# 08-DPLL-2.net
KiCad netlist of a schematic drawn in Altium Designer
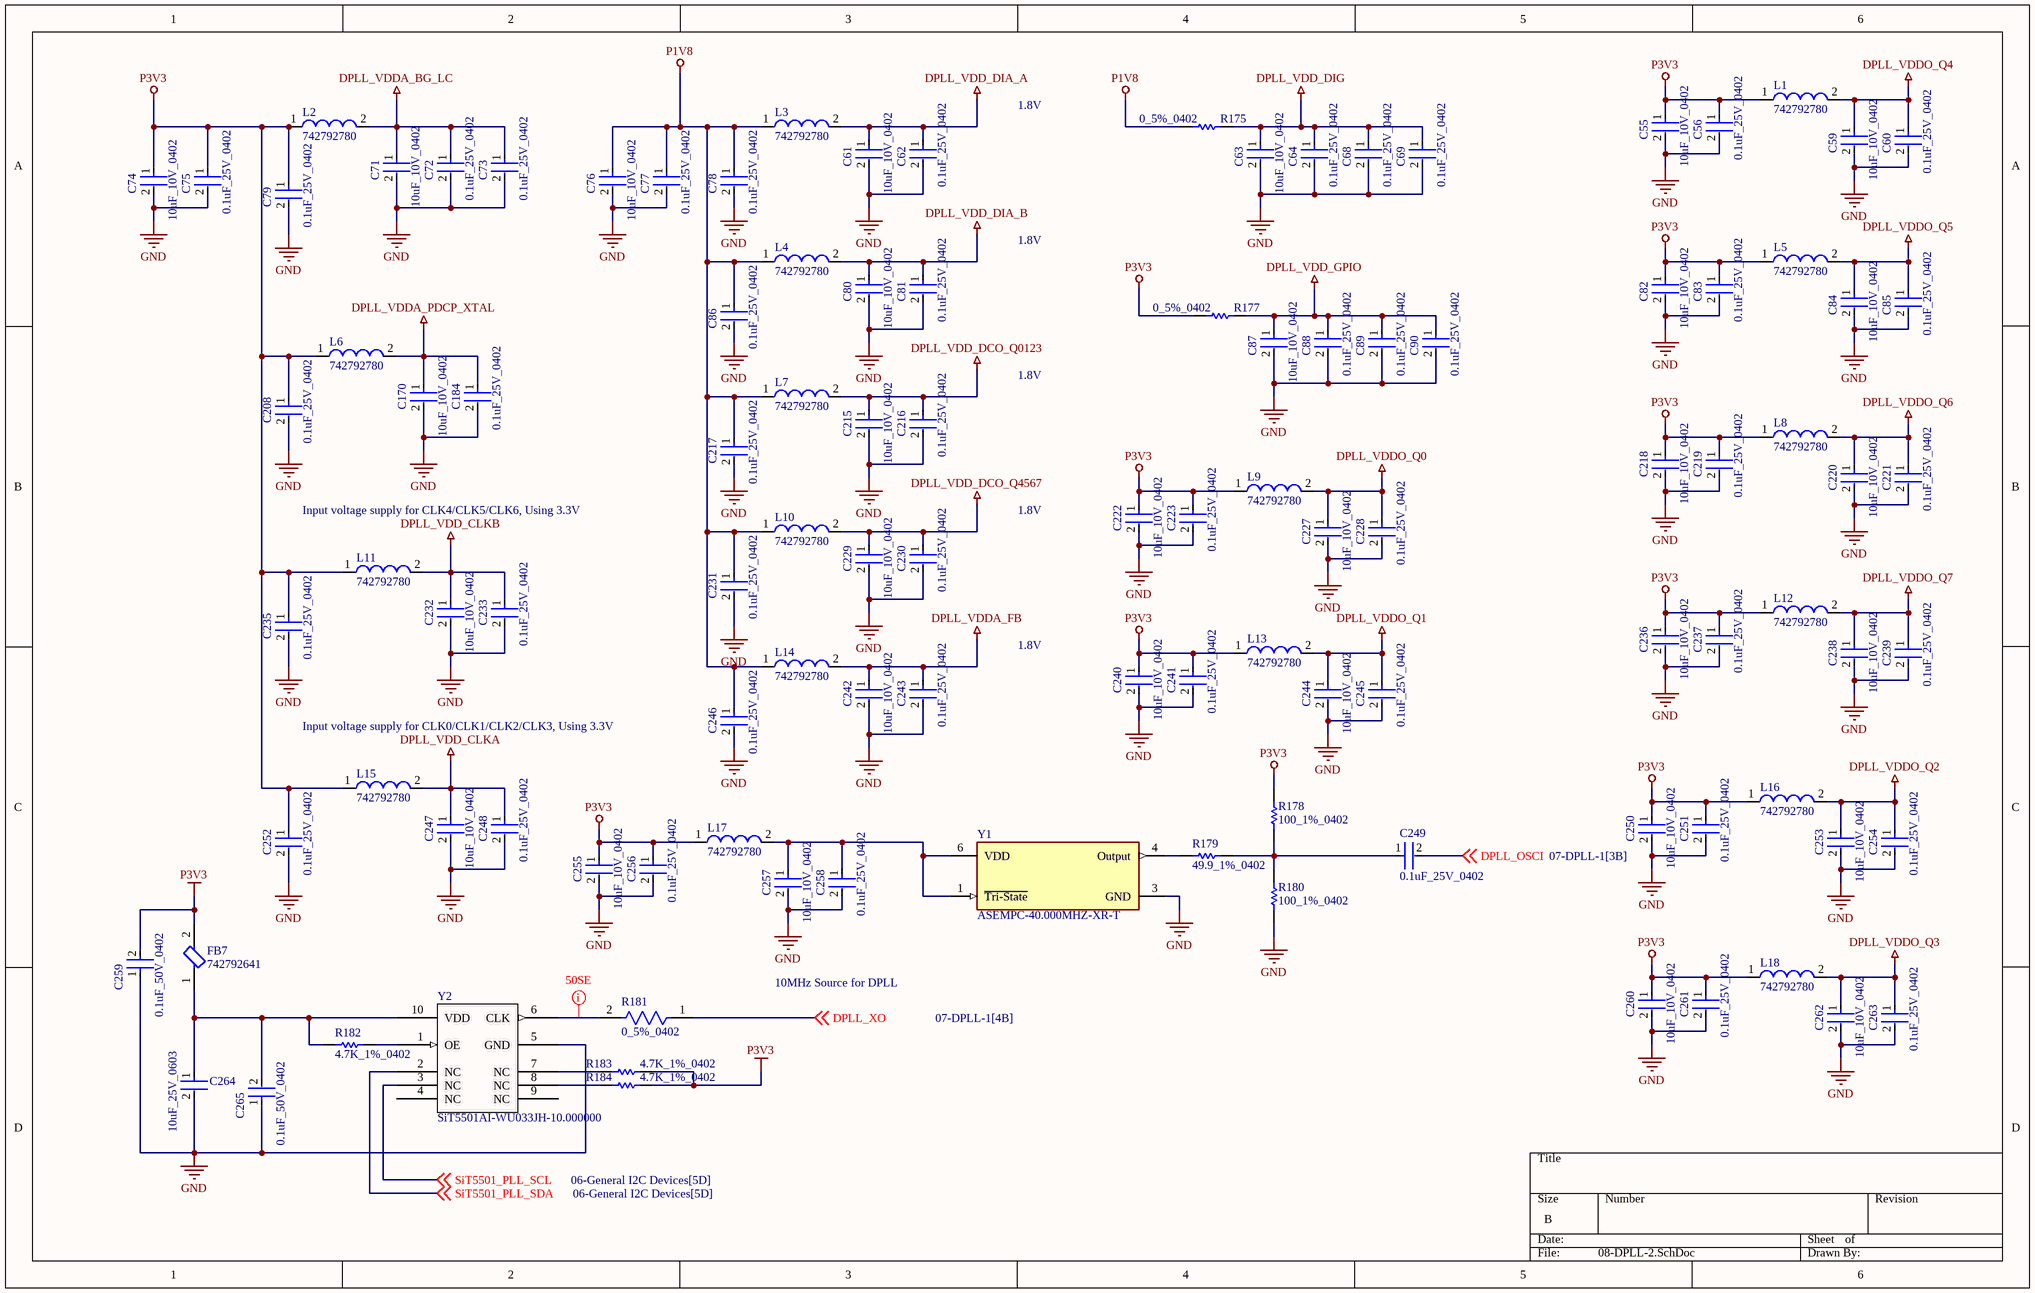
[diagram p0: 08-DPLL-2.SchDoc]

(export (version "E")
  (design (tool "Eeschema 10.0.6"))
  (components
    (comp (ref "C55")
      (value "10uF_10V_0402")
      (footprint "FP-CL05A106MP5NUNC-MFG")
      (description "CAP CER 10UF 10V X5R 0402")
      (fields
        (field (name "OCTOPART") "https://octopart.com/cl05a106mp5nunc-samsung-22457395")
        (field (name "TOLERANCE") "20%")
      )
      (libsource (lib "Altium Content Vault") (part "b4654b650e69147ec39a6b967a45e02"))
    )
    (comp (ref "C56")
      (value "0.1uF_25V_0402")
      (footprint "FP-0402-L_1_0_1-W_0_5_0_1-IPC_C")
      (description "General Purpose Ceramic Capacitor, 0402, 100nF, 10%, X7R, 15%, 25V")
      (fields (field (name "VOLTAGE") "25V") (field (name "TOLERANCE") "10%"))
      (libsource (lib "Altium Content Vault") (part "b4654b650e69147ec39a6b967a45e02"))
    )
    (comp (ref "C59")
      (value "10uF_10V_0402")
      (footprint "FP-CL05A106MP5NUNC-MFG")
      (description "CAP CER 10UF 10V X5R 0402")
      (fields
        (field (name "OCTOPART") "https://octopart.com/cl05a106mp5nunc-samsung-22457395")
        (field (name "TOLERANCE") "20%")
      )
      (libsource (lib "Altium Content Vault") (part "b4654b650e69147ec39a6b967a45e02"))
    )
    (comp (ref "C60")
      (value "0.1uF_25V_0402")
      (footprint "FP-0402-L_1_0_1-W_0_5_0_1-IPC_C")
      (description "General Purpose Ceramic Capacitor, 0402, 100nF, 10%, X7R, 15%, 25V")
      (fields (field (name "VOLTAGE") "25V") (field (name "TOLERANCE") "10%"))
      (libsource (lib "Altium Content Vault") (part "b4654b650e69147ec39a6b967a45e02"))
    )
    (comp (ref "C61")
      (value "10uF_10V_0402")
      (footprint "FP-CL05A106MP5NUNC-MFG")
      (description "CAP CER 10UF 10V X5R 0402")
      (fields
        (field (name "OCTOPART") "https://octopart.com/cl05a106mp5nunc-samsung-22457395")
        (field (name "TOLERANCE") "20%")
      )
      (libsource (lib "Altium Content Vault") (part "b4654b650e69147ec39a6b967a45e02"))
    )
    (comp (ref "C62")
      (value "0.1uF_25V_0402")
      (footprint "FP-0402-L_1_0_1-W_0_5_0_1-IPC_C")
      (description "General Purpose Ceramic Capacitor, 0402, 100nF, 10%, X7R, 15%, 25V")
      (fields (field (name "VOLTAGE") "25V") (field (name "TOLERANCE") "10%"))
      (libsource (lib "Altium Content Vault") (part "b4654b650e69147ec39a6b967a45e02"))
    )
    (comp (ref "C63")
      (value "10uF_10V_0402")
      (footprint "FP-CL05A106MP5NUNC-MFG")
      (description "CAP CER 10UF 10V X5R 0402")
      (fields
        (field (name "OCTOPART") "https://octopart.com/cl05a106mp5nunc-samsung-22457395")
        (field (name "TOLERANCE") "20%")
      )
      (libsource (lib "Altium Content Vault") (part "b4654b650e69147ec39a6b967a45e02"))
    )
    (comp (ref "C64")
      (value "0.1uF_25V_0402")
      (footprint "FP-0402-L_1_0_1-W_0_5_0_1-IPC_C")
      (description "General Purpose Ceramic Capacitor, 0402, 100nF, 10%, X7R, 15%, 25V")
      (fields (field (name "VOLTAGE") "25V") (field (name "TOLERANCE") "10%"))
      (libsource (lib "Altium Content Vault") (part "b4654b650e69147ec39a6b967a45e02"))
    )
    (comp (ref "C68")
      (value "0.1uF_25V_0402")
      (footprint "FP-0402-L_1_0_1-W_0_5_0_1-IPC_C")
      (description "General Purpose Ceramic Capacitor, 0402, 100nF, 10%, X7R, 15%, 25V")
      (fields (field (name "VOLTAGE") "25V") (field (name "TOLERANCE") "10%"))
      (libsource (lib "Altium Content Vault") (part "b4654b650e69147ec39a6b967a45e02"))
    )
    (comp (ref "C69")
      (value "0.1uF_25V_0402")
      (footprint "FP-0402-L_1_0_1-W_0_5_0_1-IPC_C")
      (description "General Purpose Ceramic Capacitor, 0402, 100nF, 10%, X7R, 15%, 25V")
      (fields (field (name "VOLTAGE") "25V") (field (name "TOLERANCE") "10%"))
      (libsource (lib "Altium Content Vault") (part "b4654b650e69147ec39a6b967a45e02"))
    )
    (comp (ref "C71")
      (value "10uF_10V_0402")
      (footprint "FP-CL05A106MP5NUNC-MFG")
      (description "CAP CER 10UF 10V X5R 0402")
      (fields
        (field (name "OCTOPART") "https://octopart.com/cl05a106mp5nunc-samsung-22457395")
        (field (name "TOLERANCE") "20%")
      )
      (libsource (lib "Altium Content Vault") (part "b4654b650e69147ec39a6b967a45e02"))
    )
    (comp (ref "C72")
      (value "0.1uF_25V_0402")
      (footprint "FP-0402-L_1_0_1-W_0_5_0_1-IPC_C")
      (description "General Purpose Ceramic Capacitor, 0402, 100nF, 10%, X7R, 15%, 25V")
      (fields (field (name "VOLTAGE") "25V") (field (name "TOLERANCE") "10%"))
      (libsource (lib "Altium Content Vault") (part "b4654b650e69147ec39a6b967a45e02"))
    )
    (comp (ref "C73")
      (value "0.1uF_25V_0402")
      (footprint "FP-0402-L_1_0_1-W_0_5_0_1-IPC_C")
      (description "General Purpose Ceramic Capacitor, 0402, 100nF, 10%, X7R, 15%, 25V")
      (fields (field (name "VOLTAGE") "25V") (field (name "TOLERANCE") "10%"))
      (libsource (lib "Altium Content Vault") (part "b4654b650e69147ec39a6b967a45e02"))
    )
    (comp (ref "C74")
      (value "10uF_10V_0402")
      (footprint "FP-CL05A106MP5NUNC-MFG")
      (description "CAP CER 10UF 10V X5R 0402")
      (fields
        (field (name "OCTOPART") "https://octopart.com/cl05a106mp5nunc-samsung-22457395")
        (field (name "TOLERANCE") "20%")
      )
      (libsource (lib "Altium Content Vault") (part "b4654b650e69147ec39a6b967a45e02"))
    )
    (comp (ref "C75")
      (value "0.1uF_25V_0402")
      (footprint "FP-0402-L_1_0_1-W_0_5_0_1-IPC_C")
      (description "General Purpose Ceramic Capacitor, 0402, 100nF, 10%, X7R, 15%, 25V")
      (fields (field (name "VOLTAGE") "25V") (field (name "TOLERANCE") "10%"))
      (libsource (lib "Altium Content Vault") (part "b4654b650e69147ec39a6b967a45e02"))
    )
    (comp (ref "C76")
      (value "10uF_10V_0402")
      (footprint "FP-CL05A106MP5NUNC-MFG")
      (description "CAP CER 10UF 10V X5R 0402")
      (fields
        (field (name "OCTOPART") "https://octopart.com/cl05a106mp5nunc-samsung-22457395")
        (field (name "TOLERANCE") "20%")
      )
      (libsource (lib "Altium Content Vault") (part "b4654b650e69147ec39a6b967a45e02"))
    )
    (comp (ref "C77")
      (value "0.1uF_25V_0402")
      (footprint "FP-0402-L_1_0_1-W_0_5_0_1-IPC_C")
      (description "General Purpose Ceramic Capacitor, 0402, 100nF, 10%, X7R, 15%, 25V")
      (fields (field (name "VOLTAGE") "25V") (field (name "TOLERANCE") "10%"))
      (libsource (lib "Altium Content Vault") (part "b4654b650e69147ec39a6b967a45e02"))
    )
    (comp (ref "C78")
      (value "0.1uF_25V_0402")
      (footprint "FP-0402-L_1_0_1-W_0_5_0_1-IPC_C")
      (description "General Purpose Ceramic Capacitor, 0402, 100nF, 10%, X7R, 15%, 25V")
      (fields (field (name "VOLTAGE") "25V") (field (name "TOLERANCE") "10%"))
      (libsource (lib "Altium Content Vault") (part "b4654b650e69147ec39a6b967a45e02"))
    )
    (comp (ref "C79")
      (value "0.1uF_25V_0402")
      (footprint "FP-0402-L_1_0_1-W_0_5_0_1-IPC_C")
      (description "General Purpose Ceramic Capacitor, 0402, 100nF, 10%, X7R, 15%, 25V")
      (fields (field (name "VOLTAGE") "25V") (field (name "TOLERANCE") "10%"))
      (libsource (lib "Altium Content Vault") (part "b4654b650e69147ec39a6b967a45e02"))
    )
    (comp (ref "C80")
      (value "10uF_10V_0402")
      (footprint "FP-CL05A106MP5NUNC-MFG")
      (description "CAP CER 10UF 10V X5R 0402")
      (fields
        (field (name "OCTOPART") "https://octopart.com/cl05a106mp5nunc-samsung-22457395")
        (field (name "TOLERANCE") "20%")
      )
      (libsource (lib "Altium Content Vault") (part "b4654b650e69147ec39a6b967a45e02"))
    )
    (comp (ref "C81")
      (value "0.1uF_25V_0402")
      (footprint "FP-0402-L_1_0_1-W_0_5_0_1-IPC_C")
      (description "General Purpose Ceramic Capacitor, 0402, 100nF, 10%, X7R, 15%, 25V")
      (fields (field (name "VOLTAGE") "25V") (field (name "TOLERANCE") "10%"))
      (libsource (lib "Altium Content Vault") (part "b4654b650e69147ec39a6b967a45e02"))
    )
    (comp (ref "C82")
      (value "10uF_10V_0402")
      (footprint "FP-CL05A106MP5NUNC-MFG")
      (description "CAP CER 10UF 10V X5R 0402")
      (fields
        (field (name "OCTOPART") "https://octopart.com/cl05a106mp5nunc-samsung-22457395")
        (field (name "TOLERANCE") "20%")
      )
      (libsource (lib "Altium Content Vault") (part "b4654b650e69147ec39a6b967a45e02"))
    )
    (comp (ref "C83")
      (value "0.1uF_25V_0402")
      (footprint "FP-0402-L_1_0_1-W_0_5_0_1-IPC_C")
      (description "General Purpose Ceramic Capacitor, 0402, 100nF, 10%, X7R, 15%, 25V")
      (fields (field (name "VOLTAGE") "25V") (field (name "TOLERANCE") "10%"))
      (libsource (lib "Altium Content Vault") (part "b4654b650e69147ec39a6b967a45e02"))
    )
    (comp (ref "C84")
      (value "10uF_10V_0402")
      (footprint "FP-CL05A106MP5NUNC-MFG")
      (description "CAP CER 10UF 10V X5R 0402")
      (fields
        (field (name "OCTOPART") "https://octopart.com/cl05a106mp5nunc-samsung-22457395")
        (field (name "TOLERANCE") "20%")
      )
      (libsource (lib "Altium Content Vault") (part "b4654b650e69147ec39a6b967a45e02"))
    )
    (comp (ref "C85")
      (value "0.1uF_25V_0402")
      (footprint "FP-0402-L_1_0_1-W_0_5_0_1-IPC_C")
      (description "General Purpose Ceramic Capacitor, 0402, 100nF, 10%, X7R, 15%, 25V")
      (fields (field (name "VOLTAGE") "25V") (field (name "TOLERANCE") "10%"))
      (libsource (lib "Altium Content Vault") (part "b4654b650e69147ec39a6b967a45e02"))
    )
    (comp (ref "C86")
      (value "0.1uF_25V_0402")
      (footprint "FP-0402-L_1_0_1-W_0_5_0_1-IPC_C")
      (description "General Purpose Ceramic Capacitor, 0402, 100nF, 10%, X7R, 15%, 25V")
      (fields (field (name "VOLTAGE") "25V") (field (name "TOLERANCE") "10%"))
      (libsource (lib "Altium Content Vault") (part "b4654b650e69147ec39a6b967a45e02"))
    )
    (comp (ref "C87")
      (value "10uF_10V_0402")
      (footprint "FP-CL05A106MP5NUNC-MFG")
      (description "CAP CER 10UF 10V X5R 0402")
      (fields
        (field (name "OCTOPART") "https://octopart.com/cl05a106mp5nunc-samsung-22457395")
        (field (name "TOLERANCE") "20%")
      )
      (libsource (lib "Altium Content Vault") (part "b4654b650e69147ec39a6b967a45e02"))
    )
    (comp (ref "C88")
      (value "0.1uF_25V_0402")
      (footprint "FP-0402-L_1_0_1-W_0_5_0_1-IPC_C")
      (description "General Purpose Ceramic Capacitor, 0402, 100nF, 10%, X7R, 15%, 25V")
      (fields (field (name "VOLTAGE") "25V") (field (name "TOLERANCE") "10%"))
      (libsource (lib "Altium Content Vault") (part "b4654b650e69147ec39a6b967a45e02"))
    )
    (comp (ref "C89")
      (value "0.1uF_25V_0402")
      (footprint "FP-0402-L_1_0_1-W_0_5_0_1-IPC_C")
      (description "General Purpose Ceramic Capacitor, 0402, 100nF, 10%, X7R, 15%, 25V")
      (fields (field (name "VOLTAGE") "25V") (field (name "TOLERANCE") "10%"))
      (libsource (lib "Altium Content Vault") (part "b4654b650e69147ec39a6b967a45e02"))
    )
    (comp (ref "C90")
      (value "0.1uF_25V_0402")
      (footprint "FP-0402-L_1_0_1-W_0_5_0_1-IPC_C")
      (description "General Purpose Ceramic Capacitor, 0402, 100nF, 10%, X7R, 15%, 25V")
      (fields (field (name "VOLTAGE") "25V") (field (name "TOLERANCE") "10%"))
      (libsource (lib "Altium Content Vault") (part "b4654b650e69147ec39a6b967a45e02"))
    )
    (comp (ref "C170")
      (value "10uF_10V_0402")
      (footprint "FP-CL05A106MP5NUNC-MFG")
      (description "CAP CER 10UF 10V X5R 0402")
      (fields
        (field (name "OCTOPART") "https://octopart.com/cl05a106mp5nunc-samsung-22457395")
        (field (name "TOLERANCE") "20%")
      )
      (libsource (lib "Altium Content Vault") (part "b4654b650e69147ec39a6b967a45e02"))
    )
    (comp (ref "C184")
      (value "0.1uF_25V_0402")
      (footprint "FP-0402-L_1_0_1-W_0_5_0_1-IPC_C")
      (description "General Purpose Ceramic Capacitor, 0402, 100nF, 10%, X7R, 15%, 25V")
      (fields (field (name "VOLTAGE") "25V") (field (name "TOLERANCE") "10%"))
      (libsource (lib "Altium Content Vault") (part "b4654b650e69147ec39a6b967a45e02"))
    )
    (comp (ref "C208")
      (value "0.1uF_25V_0402")
      (footprint "FP-0402-L_1_0_1-W_0_5_0_1-IPC_C")
      (description "General Purpose Ceramic Capacitor, 0402, 100nF, 10%, X7R, 15%, 25V")
      (fields (field (name "VOLTAGE") "25V") (field (name "TOLERANCE") "10%"))
      (libsource (lib "Altium Content Vault") (part "b4654b650e69147ec39a6b967a45e02"))
    )
    (comp (ref "C215")
      (value "10uF_10V_0402")
      (footprint "FP-CL05A106MP5NUNC-MFG")
      (description "CAP CER 10UF 10V X5R 0402")
      (fields
        (field (name "OCTOPART") "https://octopart.com/cl05a106mp5nunc-samsung-22457395")
        (field (name "TOLERANCE") "20%")
      )
      (libsource (lib "Altium Content Vault") (part "b4654b650e69147ec39a6b967a45e02"))
    )
    (comp (ref "C216")
      (value "0.1uF_25V_0402")
      (footprint "FP-0402-L_1_0_1-W_0_5_0_1-IPC_C")
      (description "General Purpose Ceramic Capacitor, 0402, 100nF, 10%, X7R, 15%, 25V")
      (fields (field (name "VOLTAGE") "25V") (field (name "TOLERANCE") "10%"))
      (libsource (lib "Altium Content Vault") (part "b4654b650e69147ec39a6b967a45e02"))
    )
    (comp (ref "C217")
      (value "0.1uF_25V_0402")
      (footprint "FP-0402-L_1_0_1-W_0_5_0_1-IPC_C")
      (description "General Purpose Ceramic Capacitor, 0402, 100nF, 10%, X7R, 15%, 25V")
      (fields (field (name "VOLTAGE") "25V") (field (name "TOLERANCE") "10%"))
      (libsource (lib "Altium Content Vault") (part "b4654b650e69147ec39a6b967a45e02"))
    )
    (comp (ref "C218")
      (value "10uF_10V_0402")
      (footprint "FP-CL05A106MP5NUNC-MFG")
      (description "CAP CER 10UF 10V X5R 0402")
      (fields
        (field (name "OCTOPART") "https://octopart.com/cl05a106mp5nunc-samsung-22457395")
        (field (name "TOLERANCE") "20%")
      )
      (libsource (lib "Altium Content Vault") (part "b4654b650e69147ec39a6b967a45e02"))
    )
    (comp (ref "C219")
      (value "0.1uF_25V_0402")
      (footprint "FP-0402-L_1_0_1-W_0_5_0_1-IPC_C")
      (description "General Purpose Ceramic Capacitor, 0402, 100nF, 10%, X7R, 15%, 25V")
      (fields (field (name "VOLTAGE") "25V") (field (name "TOLERANCE") "10%"))
      (libsource (lib "Altium Content Vault") (part "b4654b650e69147ec39a6b967a45e02"))
    )
    (comp (ref "C220")
      (value "10uF_10V_0402")
      (footprint "FP-CL05A106MP5NUNC-MFG")
      (description "CAP CER 10UF 10V X5R 0402")
      (fields
        (field (name "OCTOPART") "https://octopart.com/cl05a106mp5nunc-samsung-22457395")
        (field (name "TOLERANCE") "20%")
      )
      (libsource (lib "Altium Content Vault") (part "b4654b650e69147ec39a6b967a45e02"))
    )
    (comp (ref "C221")
      (value "0.1uF_25V_0402")
      (footprint "FP-0402-L_1_0_1-W_0_5_0_1-IPC_C")
      (description "General Purpose Ceramic Capacitor, 0402, 100nF, 10%, X7R, 15%, 25V")
      (fields (field (name "VOLTAGE") "25V") (field (name "TOLERANCE") "10%"))
      (libsource (lib "Altium Content Vault") (part "b4654b650e69147ec39a6b967a45e02"))
    )
    (comp (ref "C222")
      (value "10uF_10V_0402")
      (footprint "FP-CL05A106MP5NUNC-MFG")
      (description "CAP CER 10UF 10V X5R 0402")
      (fields
        (field (name "OCTOPART") "https://octopart.com/cl05a106mp5nunc-samsung-22457395")
        (field (name "TOLERANCE") "20%")
      )
      (libsource (lib "Altium Content Vault") (part "b4654b650e69147ec39a6b967a45e02"))
    )
    (comp (ref "C223")
      (value "0.1uF_25V_0402")
      (footprint "FP-0402-L_1_0_1-W_0_5_0_1-IPC_C")
      (description "General Purpose Ceramic Capacitor, 0402, 100nF, 10%, X7R, 15%, 25V")
      (fields (field (name "VOLTAGE") "25V") (field (name "TOLERANCE") "10%"))
      (libsource (lib "Altium Content Vault") (part "b4654b650e69147ec39a6b967a45e02"))
    )
    (comp (ref "C227")
      (value "10uF_10V_0402")
      (footprint "FP-CL05A106MP5NUNC-MFG")
      (description "CAP CER 10UF 10V X5R 0402")
      (fields
        (field (name "OCTOPART") "https://octopart.com/cl05a106mp5nunc-samsung-22457395")
        (field (name "TOLERANCE") "20%")
      )
      (libsource (lib "Altium Content Vault") (part "b4654b650e69147ec39a6b967a45e02"))
    )
    (comp (ref "C228")
      (value "0.1uF_25V_0402")
      (footprint "FP-0402-L_1_0_1-W_0_5_0_1-IPC_C")
      (description "General Purpose Ceramic Capacitor, 0402, 100nF, 10%, X7R, 15%, 25V")
      (fields (field (name "VOLTAGE") "25V") (field (name "TOLERANCE") "10%"))
      (libsource (lib "Altium Content Vault") (part "b4654b650e69147ec39a6b967a45e02"))
    )
    (comp (ref "C229")
      (value "10uF_10V_0402")
      (footprint "FP-CL05A106MP5NUNC-MFG")
      (description "CAP CER 10UF 10V X5R 0402")
      (fields
        (field (name "OCTOPART") "https://octopart.com/cl05a106mp5nunc-samsung-22457395")
        (field (name "TOLERANCE") "20%")
      )
      (libsource (lib "Altium Content Vault") (part "b4654b650e69147ec39a6b967a45e02"))
    )
    (comp (ref "C230")
      (value "0.1uF_25V_0402")
      (footprint "FP-0402-L_1_0_1-W_0_5_0_1-IPC_C")
      (description "General Purpose Ceramic Capacitor, 0402, 100nF, 10%, X7R, 15%, 25V")
      (fields (field (name "VOLTAGE") "25V") (field (name "TOLERANCE") "10%"))
      (libsource (lib "Altium Content Vault") (part "b4654b650e69147ec39a6b967a45e02"))
    )
    (comp (ref "C231")
      (value "0.1uF_25V_0402")
      (footprint "FP-0402-L_1_0_1-W_0_5_0_1-IPC_C")
      (description "General Purpose Ceramic Capacitor, 0402, 100nF, 10%, X7R, 15%, 25V")
      (fields (field (name "VOLTAGE") "25V") (field (name "TOLERANCE") "10%"))
      (libsource (lib "Altium Content Vault") (part "b4654b650e69147ec39a6b967a45e02"))
    )
    (comp (ref "C232")
      (value "10uF_10V_0402")
      (footprint "FP-CL05A106MP5NUNC-MFG")
      (description "CAP CER 10UF 10V X5R 0402")
      (fields
        (field (name "OCTOPART") "https://octopart.com/cl05a106mp5nunc-samsung-22457395")
        (field (name "TOLERANCE") "20%")
      )
      (libsource (lib "Altium Content Vault") (part "b4654b650e69147ec39a6b967a45e02"))
    )
    (comp (ref "C233")
      (value "0.1uF_25V_0402")
      (footprint "FP-0402-L_1_0_1-W_0_5_0_1-IPC_C")
      (description "General Purpose Ceramic Capacitor, 0402, 100nF, 10%, X7R, 15%, 25V")
      (fields (field (name "VOLTAGE") "25V") (field (name "TOLERANCE") "10%"))
      (libsource (lib "Altium Content Vault") (part "b4654b650e69147ec39a6b967a45e02"))
    )
    (comp (ref "C235")
      (value "0.1uF_25V_0402")
      (footprint "FP-0402-L_1_0_1-W_0_5_0_1-IPC_C")
      (description "General Purpose Ceramic Capacitor, 0402, 100nF, 10%, X7R, 15%, 25V")
      (fields (field (name "VOLTAGE") "25V") (field (name "TOLERANCE") "10%"))
      (libsource (lib "Altium Content Vault") (part "b4654b650e69147ec39a6b967a45e02"))
    )
    (comp (ref "C236")
      (value "10uF_10V_0402")
      (footprint "FP-CL05A106MP5NUNC-MFG")
      (description "CAP CER 10UF 10V X5R 0402")
      (fields
        (field (name "OCTOPART") "https://octopart.com/cl05a106mp5nunc-samsung-22457395")
        (field (name "TOLERANCE") "20%")
      )
      (libsource (lib "Altium Content Vault") (part "b4654b650e69147ec39a6b967a45e02"))
    )
    (comp (ref "C237")
      (value "0.1uF_25V_0402")
      (footprint "FP-0402-L_1_0_1-W_0_5_0_1-IPC_C")
      (description "General Purpose Ceramic Capacitor, 0402, 100nF, 10%, X7R, 15%, 25V")
      (fields (field (name "VOLTAGE") "25V") (field (name "TOLERANCE") "10%"))
      (libsource (lib "Altium Content Vault") (part "b4654b650e69147ec39a6b967a45e02"))
    )
    (comp (ref "C238")
      (value "10uF_10V_0402")
      (footprint "FP-CL05A106MP5NUNC-MFG")
      (description "CAP CER 10UF 10V X5R 0402")
      (fields
        (field (name "OCTOPART") "https://octopart.com/cl05a106mp5nunc-samsung-22457395")
        (field (name "TOLERANCE") "20%")
      )
      (libsource (lib "Altium Content Vault") (part "b4654b650e69147ec39a6b967a45e02"))
    )
    (comp (ref "C239")
      (value "0.1uF_25V_0402")
      (footprint "FP-0402-L_1_0_1-W_0_5_0_1-IPC_C")
      (description "General Purpose Ceramic Capacitor, 0402, 100nF, 10%, X7R, 15%, 25V")
      (fields (field (name "VOLTAGE") "25V") (field (name "TOLERANCE") "10%"))
      (libsource (lib "Altium Content Vault") (part "b4654b650e69147ec39a6b967a45e02"))
    )
    (comp (ref "C240")
      (value "10uF_10V_0402")
      (footprint "FP-CL05A106MP5NUNC-MFG")
      (description "CAP CER 10UF 10V X5R 0402")
      (fields
        (field (name "OCTOPART") "https://octopart.com/cl05a106mp5nunc-samsung-22457395")
        (field (name "TOLERANCE") "20%")
      )
      (libsource (lib "Altium Content Vault") (part "b4654b650e69147ec39a6b967a45e02"))
    )
    (comp (ref "C241")
      (value "0.1uF_25V_0402")
      (footprint "FP-0402-L_1_0_1-W_0_5_0_1-IPC_C")
      (description "General Purpose Ceramic Capacitor, 0402, 100nF, 10%, X7R, 15%, 25V")
      (fields (field (name "VOLTAGE") "25V") (field (name "TOLERANCE") "10%"))
      (libsource (lib "Altium Content Vault") (part "b4654b650e69147ec39a6b967a45e02"))
    )
    (comp (ref "C242")
      (value "10uF_10V_0402")
      (footprint "FP-CL05A106MP5NUNC-MFG")
      (description "CAP CER 10UF 10V X5R 0402")
      (fields
        (field (name "OCTOPART") "https://octopart.com/cl05a106mp5nunc-samsung-22457395")
        (field (name "TOLERANCE") "20%")
      )
      (libsource (lib "Altium Content Vault") (part "b4654b650e69147ec39a6b967a45e02"))
    )
    (comp (ref "C243")
      (value "0.1uF_25V_0402")
      (footprint "FP-0402-L_1_0_1-W_0_5_0_1-IPC_C")
      (description "General Purpose Ceramic Capacitor, 0402, 100nF, 10%, X7R, 15%, 25V")
      (fields (field (name "VOLTAGE") "25V") (field (name "TOLERANCE") "10%"))
      (libsource (lib "Altium Content Vault") (part "b4654b650e69147ec39a6b967a45e02"))
    )
    (comp (ref "C244")
      (value "10uF_10V_0402")
      (footprint "FP-CL05A106MP5NUNC-MFG")
      (description "CAP CER 10UF 10V X5R 0402")
      (fields
        (field (name "OCTOPART") "https://octopart.com/cl05a106mp5nunc-samsung-22457395")
        (field (name "TOLERANCE") "20%")
      )
      (libsource (lib "Altium Content Vault") (part "b4654b650e69147ec39a6b967a45e02"))
    )
    (comp (ref "C245")
      (value "0.1uF_25V_0402")
      (footprint "FP-0402-L_1_0_1-W_0_5_0_1-IPC_C")
      (description "General Purpose Ceramic Capacitor, 0402, 100nF, 10%, X7R, 15%, 25V")
      (fields (field (name "VOLTAGE") "25V") (field (name "TOLERANCE") "10%"))
      (libsource (lib "Altium Content Vault") (part "b4654b650e69147ec39a6b967a45e02"))
    )
    (comp (ref "C246")
      (value "0.1uF_25V_0402")
      (footprint "FP-0402-L_1_0_1-W_0_5_0_1-IPC_C")
      (description "General Purpose Ceramic Capacitor, 0402, 100nF, 10%, X7R, 15%, 25V")
      (fields (field (name "VOLTAGE") "25V") (field (name "TOLERANCE") "10%"))
      (libsource (lib "Altium Content Vault") (part "b4654b650e69147ec39a6b967a45e02"))
    )
    (comp (ref "C247")
      (value "10uF_10V_0402")
      (footprint "FP-CL05A106MP5NUNC-MFG")
      (description "CAP CER 10UF 10V X5R 0402")
      (fields
        (field (name "OCTOPART") "https://octopart.com/cl05a106mp5nunc-samsung-22457395")
        (field (name "TOLERANCE") "20%")
      )
      (libsource (lib "Altium Content Vault") (part "b4654b650e69147ec39a6b967a45e02"))
    )
    (comp (ref "C248")
      (value "0.1uF_25V_0402")
      (footprint "FP-0402-L_1_0_1-W_0_5_0_1-IPC_C")
      (description "General Purpose Ceramic Capacitor, 0402, 100nF, 10%, X7R, 15%, 25V")
      (fields (field (name "VOLTAGE") "25V") (field (name "TOLERANCE") "10%"))
      (libsource (lib "Altium Content Vault") (part "b4654b650e69147ec39a6b967a45e02"))
    )
    (comp (ref "C249")
      (value "0.1uF_25V_0402")
      (footprint "FP-0402-L_1_0_1-W_0_5_0_1-IPC_C")
      (description "General Purpose Ceramic Capacitor, 0402, 100nF, 10%, X7R, 15%, 25V")
      (fields (field (name "VOLTAGE") "25V") (field (name "TOLERANCE") "10%"))
      (libsource (lib "Altium Content Vault") (part "b4654b650e69147ec39a6b967a45e02"))
    )
    (comp (ref "C250")
      (value "10uF_10V_0402")
      (footprint "FP-CL05A106MP5NUNC-MFG")
      (description "CAP CER 10UF 10V X5R 0402")
      (fields
        (field (name "OCTOPART") "https://octopart.com/cl05a106mp5nunc-samsung-22457395")
        (field (name "TOLERANCE") "20%")
      )
      (libsource (lib "Altium Content Vault") (part "b4654b650e69147ec39a6b967a45e02"))
    )
    (comp (ref "C251")
      (value "0.1uF_25V_0402")
      (footprint "FP-0402-L_1_0_1-W_0_5_0_1-IPC_C")
      (description "General Purpose Ceramic Capacitor, 0402, 100nF, 10%, X7R, 15%, 25V")
      (fields (field (name "VOLTAGE") "25V") (field (name "TOLERANCE") "10%"))
      (libsource (lib "Altium Content Vault") (part "b4654b650e69147ec39a6b967a45e02"))
    )
    (comp (ref "C252")
      (value "0.1uF_25V_0402")
      (footprint "FP-0402-L_1_0_1-W_0_5_0_1-IPC_C")
      (description "General Purpose Ceramic Capacitor, 0402, 100nF, 10%, X7R, 15%, 25V")
      (fields (field (name "VOLTAGE") "25V") (field (name "TOLERANCE") "10%"))
      (libsource (lib "Altium Content Vault") (part "b4654b650e69147ec39a6b967a45e02"))
    )
    (comp (ref "C253")
      (value "10uF_10V_0402")
      (footprint "FP-CL05A106MP5NUNC-MFG")
      (description "CAP CER 10UF 10V X5R 0402")
      (fields
        (field (name "OCTOPART") "https://octopart.com/cl05a106mp5nunc-samsung-22457395")
        (field (name "TOLERANCE") "20%")
      )
      (libsource (lib "Altium Content Vault") (part "b4654b650e69147ec39a6b967a45e02"))
    )
    (comp (ref "C254")
      (value "0.1uF_25V_0402")
      (footprint "FP-0402-L_1_0_1-W_0_5_0_1-IPC_C")
      (description "General Purpose Ceramic Capacitor, 0402, 100nF, 10%, X7R, 15%, 25V")
      (fields (field (name "VOLTAGE") "25V") (field (name "TOLERANCE") "10%"))
      (libsource (lib "Altium Content Vault") (part "b4654b650e69147ec39a6b967a45e02"))
    )
    (comp (ref "C255")
      (value "10uF_10V_0402")
      (footprint "FP-CL05A106MP5NUNC-MFG")
      (description "CAP CER 10UF 10V X5R 0402")
      (fields
        (field (name "OCTOPART") "https://octopart.com/cl05a106mp5nunc-samsung-22457395")
        (field (name "TOLERANCE") "20%")
      )
      (libsource (lib "Altium Content Vault") (part "b4654b650e69147ec39a6b967a45e02"))
    )
    (comp (ref "C256")
      (value "0.1uF_25V_0402")
      (footprint "FP-0402-L_1_0_1-W_0_5_0_1-IPC_C")
      (description "General Purpose Ceramic Capacitor, 0402, 100nF, 10%, X7R, 15%, 25V")
      (fields (field (name "VOLTAGE") "25V") (field (name "TOLERANCE") "10%"))
      (libsource (lib "Altium Content Vault") (part "b4654b650e69147ec39a6b967a45e02"))
    )
    (comp (ref "C257")
      (value "10uF_10V_0402")
      (footprint "FP-CL05A106MP5NUNC-MFG")
      (description "CAP CER 10UF 10V X5R 0402")
      (fields
        (field (name "OCTOPART") "https://octopart.com/cl05a106mp5nunc-samsung-22457395")
        (field (name "TOLERANCE") "20%")
      )
      (libsource (lib "Altium Content Vault") (part "b4654b650e69147ec39a6b967a45e02"))
    )
    (comp (ref "C258")
      (value "0.1uF_25V_0402")
      (footprint "FP-0402-L_1_0_1-W_0_5_0_1-IPC_C")
      (description "General Purpose Ceramic Capacitor, 0402, 100nF, 10%, X7R, 15%, 25V")
      (fields (field (name "VOLTAGE") "25V") (field (name "TOLERANCE") "10%"))
      (libsource (lib "Altium Content Vault") (part "b4654b650e69147ec39a6b967a45e02"))
    )
    (comp (ref "C259")
      (value "0.1uF_50V_0402")
      (footprint "FP-C1005-050-0_05-IPC_C")
      (description "Multilayer Ceramic Capacitors 100nF ±10% 50V X7R SMD 0402")
      (fields (field (name "VOLTAGE") "50V") (field (name "TOLERANCE") "10%"))
      (libsource (lib "Altium Content Vault") (part "b4654b650e69147ec39a6b967a45e02"))
    )
    (comp (ref "C260")
      (value "10uF_10V_0402")
      (footprint "FP-CL05A106MP5NUNC-MFG")
      (description "CAP CER 10UF 10V X5R 0402")
      (fields
        (field (name "OCTOPART") "https://octopart.com/cl05a106mp5nunc-samsung-22457395")
        (field (name "TOLERANCE") "20%")
      )
      (libsource (lib "Altium Content Vault") (part "b4654b650e69147ec39a6b967a45e02"))
    )
    (comp (ref "C261")
      (value "0.1uF_25V_0402")
      (footprint "FP-0402-L_1_0_1-W_0_5_0_1-IPC_C")
      (description "General Purpose Ceramic Capacitor, 0402, 100nF, 10%, X7R, 15%, 25V")
      (fields (field (name "VOLTAGE") "25V") (field (name "TOLERANCE") "10%"))
      (libsource (lib "Altium Content Vault") (part "b4654b650e69147ec39a6b967a45e02"))
    )
    (comp (ref "C262")
      (value "10uF_10V_0402")
      (footprint "FP-CL05A106MP5NUNC-MFG")
      (description "CAP CER 10UF 10V X5R 0402")
      (fields
        (field (name "OCTOPART") "https://octopart.com/cl05a106mp5nunc-samsung-22457395")
        (field (name "TOLERANCE") "20%")
      )
      (libsource (lib "Altium Content Vault") (part "b4654b650e69147ec39a6b967a45e02"))
    )
    (comp (ref "C263")
      (value "0.1uF_25V_0402")
      (footprint "FP-0402-L_1_0_1-W_0_5_0_1-IPC_C")
      (description "General Purpose Ceramic Capacitor, 0402, 100nF, 10%, X7R, 15%, 25V")
      (fields (field (name "VOLTAGE") "25V") (field (name "TOLERANCE") "10%"))
      (libsource (lib "Altium Content Vault") (part "b4654b650e69147ec39a6b967a45e02"))
    )
    (comp (ref "C264")
      (value "10uF_25V_0603")
      (footprint "FP-CL10-IPC_C")
      (description "Cap Ceramic 10uF 25V X5R ±20% Pad SMD 0603 +85°C T/R")
      (fields (field (name "TOLERANCE") "20%"))
      (libsource (lib "Altium Content Vault") (part "b4654b650e69147ec39a6b967a45e02"))
    )
    (comp (ref "C265")
      (value "0.1uF_50V_0402")
      (footprint "FP-C1005-050-0_05-IPC_C")
      (description "Multilayer Ceramic Capacitors 100nF ±10% 50V X7R SMD 0402")
      (fields (field (name "VOLTAGE") "50V") (field (name "TOLERANCE") "10%"))
      (libsource (lib "Altium Content Vault") (part "b4654b650e69147ec39a6b967a45e02"))
    )
    (comp (ref "FB7")
      (value "742792641")
      (footprint "FP-742792641-MFG")
      (description "FERRITE BEAD 300 OHM 0603 1LN")
      (fields (field (name "TOLERANCE") "25%"))
      (libsource (lib "Altium Content Vault") (part "5f30dd21d616792df468990f7003faa"))
    )
    (comp (ref "L1")
      (value "742792780")
      (footprint "SMD-0402")
      (description "SMD EMI Suppression Ferrite Bead WE-CBF, Z = 220 Ohm")
      (libsource (lib "Altium Content Vault") (part "PAS-IND-INDUCTOR-2"))
    )
    (comp (ref "L2")
      (value "742792780")
      (footprint "SMD-0402")
      (description "SMD EMI Suppression Ferrite Bead WE-CBF, Z = 220 Ohm")
      (libsource (lib "Altium Content Vault") (part "PAS-IND-INDUCTOR-2"))
    )
    (comp (ref "L3")
      (value "742792780")
      (footprint "SMD-0402")
      (description "SMD EMI Suppression Ferrite Bead WE-CBF, Z = 220 Ohm")
      (libsource (lib "Altium Content Vault") (part "PAS-IND-INDUCTOR-2"))
    )
    (comp (ref "L4")
      (value "742792780")
      (footprint "SMD-0402")
      (description "SMD EMI Suppression Ferrite Bead WE-CBF, Z = 220 Ohm")
      (libsource (lib "Altium Content Vault") (part "PAS-IND-INDUCTOR-2"))
    )
    (comp (ref "L5")
      (value "742792780")
      (footprint "SMD-0402")
      (description "SMD EMI Suppression Ferrite Bead WE-CBF, Z = 220 Ohm")
      (libsource (lib "Altium Content Vault") (part "PAS-IND-INDUCTOR-2"))
    )
    (comp (ref "L6")
      (value "742792780")
      (footprint "SMD-0402")
      (description "SMD EMI Suppression Ferrite Bead WE-CBF, Z = 220 Ohm")
      (libsource (lib "Altium Content Vault") (part "PAS-IND-INDUCTOR-2"))
    )
    (comp (ref "L7")
      (value "742792780")
      (footprint "SMD-0402")
      (description "SMD EMI Suppression Ferrite Bead WE-CBF, Z = 220 Ohm")
      (libsource (lib "Altium Content Vault") (part "PAS-IND-INDUCTOR-2"))
    )
    (comp (ref "L8")
      (value "742792780")
      (footprint "SMD-0402")
      (description "SMD EMI Suppression Ferrite Bead WE-CBF, Z = 220 Ohm")
      (libsource (lib "Altium Content Vault") (part "PAS-IND-INDUCTOR-2"))
    )
    (comp (ref "L9")
      (value "742792780")
      (footprint "SMD-0402")
      (description "SMD EMI Suppression Ferrite Bead WE-CBF, Z = 220 Ohm")
      (libsource (lib "Altium Content Vault") (part "PAS-IND-INDUCTOR-2"))
    )
    (comp (ref "L10")
      (value "742792780")
      (footprint "SMD-0402")
      (description "SMD EMI Suppression Ferrite Bead WE-CBF, Z = 220 Ohm")
      (libsource (lib "Altium Content Vault") (part "PAS-IND-INDUCTOR-2"))
    )
    (comp (ref "L11")
      (value "742792780")
      (footprint "SMD-0402")
      (description "SMD EMI Suppression Ferrite Bead WE-CBF, Z = 220 Ohm")
      (libsource (lib "Altium Content Vault") (part "PAS-IND-INDUCTOR-2"))
    )
    (comp (ref "L12")
      (value "742792780")
      (footprint "SMD-0402")
      (description "SMD EMI Suppression Ferrite Bead WE-CBF, Z = 220 Ohm")
      (libsource (lib "Altium Content Vault") (part "PAS-IND-INDUCTOR-2"))
    )
    (comp (ref "L13")
      (value "742792780")
      (footprint "SMD-0402")
      (description "SMD EMI Suppression Ferrite Bead WE-CBF, Z = 220 Ohm")
      (libsource (lib "Altium Content Vault") (part "PAS-IND-INDUCTOR-2"))
    )
    (comp (ref "L14")
      (value "742792780")
      (footprint "SMD-0402")
      (description "SMD EMI Suppression Ferrite Bead WE-CBF, Z = 220 Ohm")
      (libsource (lib "Altium Content Vault") (part "PAS-IND-INDUCTOR-2"))
    )
    (comp (ref "L15")
      (value "742792780")
      (footprint "SMD-0402")
      (description "SMD EMI Suppression Ferrite Bead WE-CBF, Z = 220 Ohm")
      (libsource (lib "Altium Content Vault") (part "PAS-IND-INDUCTOR-2"))
    )
    (comp (ref "L16")
      (value "742792780")
      (footprint "SMD-0402")
      (description "SMD EMI Suppression Ferrite Bead WE-CBF, Z = 220 Ohm")
      (libsource (lib "Altium Content Vault") (part "PAS-IND-INDUCTOR-2"))
    )
    (comp (ref "L17")
      (value "742792780")
      (footprint "SMD-0402")
      (description "SMD EMI Suppression Ferrite Bead WE-CBF, Z = 220 Ohm")
      (libsource (lib "Altium Content Vault") (part "PAS-IND-INDUCTOR-2"))
    )
    (comp (ref "L18")
      (value "742792780")
      (footprint "SMD-0402")
      (description "SMD EMI Suppression Ferrite Bead WE-CBF, Z = 220 Ohm")
      (libsource (lib "Altium Content Vault") (part "PAS-IND-INDUCTOR-2"))
    )
    (comp (ref "R175")
      (value "0_5%_0402")
      (footprint "RESC1005X40X25LL10T10")
      (fields (field (name "MANUFACTURER") "KOA Speer") (field (name "PART NUMBER") "RK73Z1ETTP"))
      (libsource (lib "Altium Content Vault") (part "RES"))
    )
    (comp (ref "R177")
      (value "0_5%_0402")
      (footprint "RESC1005X40X25LL10T10")
      (fields (field (name "MANUFACTURER") "KOA Speer") (field (name "PART NUMBER") "RK73Z1ETTP"))
      (libsource (lib "Altium Content Vault") (part "RES"))
    )
    (comp (ref "R178")
      (value "100_1%_0402")
      (footprint "RESC1005X40X25ML05T10")
      (fields (field (name "PART NUMBER") "ERJ-U02F1000X") (field (name "MANUFACTURER") "Panasonic"))
      (libsource (lib "Altium Content Vault") (part "RES"))
    )
    (comp (ref "R179")
      (value "49.9_1%_0402")
      (footprint "RESC1005X40X25NL10T10")
      (fields (field (name "PART NUMBER") "RK73H1ETTP49R9F") (field (name "MANUFACTURER") "KOA Speer"))
      (libsource (lib "Altium Content Vault") (part "RES"))
    )
    (comp (ref "R180")
      (value "100_1%_0402")
      (footprint "RESC1005X40X25ML05T10")
      (fields (field (name "PART NUMBER") "ERJ-U02F1000X") (field (name "MANUFACTURER") "Panasonic"))
      (libsource (lib "Altium Content Vault") (part "RES"))
    )
    (comp (ref "R181")
      (value "0_5%_0402")
      (footprint "FP-AC0402-0_37-IPC_B")
      (description "RESISTOR 0402 JUMPER ZERO OHM")
      (fields (field (name "TOLERANCE") "1%"))
      (libsource (lib "Altium Content Vault") (part "1029c3af85768c4190bb7ad29bc67b5"))
    )
    (comp (ref "R182")
      (value "4.7K_1%_0402")
      (footprint "RESC1005X40X25NL10T10")
      (fields (field (name "MANUFACTURER") "Bourns") (field (name "PART NUMBER") "CR0402-FX-4701GLF"))
      (libsource (lib "Altium Content Vault") (part "RES"))
    )
    (comp (ref "R183")
      (value "4.7K_1%_0402")
      (footprint "RESC1005X40X25NL10T10")
      (fields (field (name "MANUFACTURER") "Bourns") (field (name "PART NUMBER") "CR0402-FX-4701GLF"))
      (libsource (lib "Altium Content Vault") (part "RES"))
    )
    (comp (ref "R184")
      (value "4.7K_1%_0402")
      (footprint "RESC1005X40X25NL10T10")
      (fields (field (name "MANUFACTURER") "Bourns") (field (name "PART NUMBER") "CR0402-FX-4701GLF"))
      (libsource (lib "Altium Content Vault") (part "RES"))
    )
    (comp (ref "Y1")
      (value "ASEMPC-40.000MHZ-XR-T")
      (footprint "FP-ASEMP-CMOS-MFG")
      (description "MEMS Oscillator 40MHz ±25ppm CMOS 2.25V~3.6V 6-SMD 3.2mm x 2.5mm")
      (libsource (lib "Altium Content Vault") (part "9526c112e3a98a1af86e8f4e974a861"))
    )
    (comp (ref "Y2")
      (value "SiTime_SiT5501AC-WU-33E0-10T")
      (footprint "SITIME_SPL-086-CQFN-010-C07050_REV_DRAFT")
      (description "OSC, MEMS, STRATUM 3E, 10.000MHZ, 10PPB STAB, LVCMOS, 3.3V, O/P EN, 7.0X5.0X2.2MM, CQFN-10")
      (fields
        (field (name "MANUFACTURER PART NUMBER") "SiT5501AI-WU033JH-10.000000")
        (field (name "MANUFACTURER") "SiTime")
      )
      (libsource (lib "OCXO_DaughterCard") (part "CMP-OSC-00029-2"))
    )
  )
  (nets
    (net (code "1") (name "DPLL_OSCI") (class "Default")
      (node (ref "C249") (pin "2") (pinfunction "2_2") (pintype "passive"))
    )
    (net (code "2") (name "DPLL_VDDA_BG_LC") (class "Default")
      (node (ref "C71") (pin "1") (pinfunction "1_1") (pintype "passive"))
      (node (ref "C72") (pin "1") (pinfunction "1_1") (pintype "passive"))
      (node (ref "C73") (pin "1") (pinfunction "1_1") (pintype "passive"))
      (node (ref "L2") (pin "2") (pinfunction "2_2") (pintype "passive"))
    )
    (net (code "3") (name "DPLL_VDDA_FB") (class "Default")
      (node (ref "C242") (pin "1") (pinfunction "1_1") (pintype "passive"))
      (node (ref "C243") (pin "1") (pinfunction "1_1") (pintype "passive"))
      (node (ref "L14") (pin "2") (pinfunction "2_2") (pintype "passive"))
    )
    (net (code "4") (name "DPLL_VDDA_PDCP_XTAL") (class "Default")
      (node (ref "C170") (pin "1") (pinfunction "1_1") (pintype "passive"))
      (node (ref "C184") (pin "1") (pinfunction "1_1") (pintype "passive"))
      (node (ref "L6") (pin "2") (pinfunction "2_2") (pintype "passive"))
    )
    (net (code "5") (name "DPLL_VDDO_Q0") (class "Default")
      (node (ref "C227") (pin "1") (pinfunction "1_1") (pintype "passive"))
      (node (ref "C228") (pin "1") (pinfunction "1_1") (pintype "passive"))
      (node (ref "L9") (pin "2") (pinfunction "2_2") (pintype "passive"))
    )
    (net (code "6") (name "DPLL_VDDO_Q1") (class "Default")
      (node (ref "C244") (pin "1") (pinfunction "1_1") (pintype "passive"))
      (node (ref "C245") (pin "1") (pinfunction "1_1") (pintype "passive"))
      (node (ref "L13") (pin "2") (pinfunction "2_2") (pintype "passive"))
    )
    (net (code "7") (name "DPLL_VDDO_Q2") (class "Default")
      (node (ref "C253") (pin "1") (pinfunction "1_1") (pintype "passive"))
      (node (ref "C254") (pin "1") (pinfunction "1_1") (pintype "passive"))
      (node (ref "L16") (pin "2") (pinfunction "2_2") (pintype "passive"))
    )
    (net (code "8") (name "DPLL_VDDO_Q3") (class "Default")
      (node (ref "C262") (pin "1") (pinfunction "1_1") (pintype "passive"))
      (node (ref "C263") (pin "1") (pinfunction "1_1") (pintype "passive"))
      (node (ref "L18") (pin "2") (pinfunction "2_2") (pintype "passive"))
    )
    (net (code "9") (name "DPLL_VDDO_Q4") (class "Default")
      (node (ref "C59") (pin "1") (pinfunction "1_1") (pintype "passive"))
      (node (ref "C60") (pin "1") (pinfunction "1_1") (pintype "passive"))
      (node (ref "L1") (pin "2") (pinfunction "2_2") (pintype "passive"))
    )
    (net (code "10") (name "DPLL_VDDO_Q5") (class "Default")
      (node (ref "C84") (pin "1") (pinfunction "1_1") (pintype "passive"))
      (node (ref "C85") (pin "1") (pinfunction "1_1") (pintype "passive"))
      (node (ref "L5") (pin "2") (pinfunction "2_2") (pintype "passive"))
    )
    (net (code "11") (name "DPLL_VDDO_Q6") (class "Default")
      (node (ref "C220") (pin "1") (pinfunction "1_1") (pintype "passive"))
      (node (ref "C221") (pin "1") (pinfunction "1_1") (pintype "passive"))
      (node (ref "L8") (pin "2") (pinfunction "2_2") (pintype "passive"))
    )
    (net (code "12") (name "DPLL_VDDO_Q7") (class "Default")
      (node (ref "C238") (pin "1") (pinfunction "1_1") (pintype "passive"))
      (node (ref "C239") (pin "1") (pinfunction "1_1") (pintype "passive"))
      (node (ref "L12") (pin "2") (pinfunction "2_2") (pintype "passive"))
    )
    (net (code "13") (name "DPLL_VDD_CLKA") (class "Default")
      (node (ref "C247") (pin "1") (pinfunction "1_1") (pintype "passive"))
      (node (ref "C248") (pin "1") (pinfunction "1_1") (pintype "passive"))
      (node (ref "L15") (pin "2") (pinfunction "2_2") (pintype "passive"))
    )
    (net (code "14") (name "DPLL_VDD_CLKB") (class "Default")
      (node (ref "C232") (pin "1") (pinfunction "1_1") (pintype "passive"))
      (node (ref "C233") (pin "1") (pinfunction "1_1") (pintype "passive"))
      (node (ref "L11") (pin "2") (pinfunction "2_2") (pintype "passive"))
    )
    (net (code "15") (name "DPLL_VDD_DCO_Q0123") (class "Default")
      (node (ref "C215") (pin "1") (pinfunction "1_1") (pintype "passive"))
      (node (ref "C216") (pin "1") (pinfunction "1_1") (pintype "passive"))
      (node (ref "L7") (pin "2") (pinfunction "2_2") (pintype "passive"))
    )
    (net (code "16") (name "DPLL_VDD_DCO_Q4567") (class "Default")
      (node (ref "C229") (pin "1") (pinfunction "1_1") (pintype "passive"))
      (node (ref "C230") (pin "1") (pinfunction "1_1") (pintype "passive"))
      (node (ref "L10") (pin "2") (pinfunction "2_2") (pintype "passive"))
    )
    (net (code "17") (name "DPLL_VDD_DIA_A") (class "Default")
      (node (ref "C61") (pin "1") (pinfunction "1_1") (pintype "passive"))
      (node (ref "C62") (pin "1") (pinfunction "1_1") (pintype "passive"))
      (node (ref "L3") (pin "2") (pinfunction "2_2") (pintype "passive"))
    )
    (net (code "18") (name "DPLL_VDD_DIA_B") (class "Default")
      (node (ref "C80") (pin "1") (pinfunction "1_1") (pintype "passive"))
      (node (ref "C81") (pin "1") (pinfunction "1_1") (pintype "passive"))
      (node (ref "L4") (pin "2") (pinfunction "2_2") (pintype "passive"))
    )
    (net (code "19") (name "DPLL_VDD_DIG") (class "Default")
      (node (ref "C63") (pin "1") (pinfunction "1_1") (pintype "passive"))
      (node (ref "C64") (pin "1") (pinfunction "1_1") (pintype "passive"))
      (node (ref "C68") (pin "1") (pinfunction "1_1") (pintype "passive"))
      (node (ref "C69") (pin "1") (pinfunction "1_1") (pintype "passive"))
      (node (ref "R175") (pin "2") (pinfunction "2_2") (pintype "passive"))
    )
    (net (code "20") (name "DPLL_VDD_GPIO") (class "Default")
      (node (ref "C87") (pin "1") (pinfunction "1_1") (pintype "passive"))
      (node (ref "C88") (pin "1") (pinfunction "1_1") (pintype "passive"))
      (node (ref "C89") (pin "1") (pinfunction "1_1") (pintype "passive"))
      (node (ref "C90") (pin "1") (pinfunction "1_1") (pintype "passive"))
      (node (ref "R177") (pin "2") (pinfunction "2_2") (pintype "passive"))
    )
    (net (code "21") (name "DPLL_XO") (class "Default")
      (node (ref "R181") (pin "1") (pinfunction "1_1") (pintype "passive"))
    )
    (net (code "22") (name "GND") (class "Default")
      (node (ref "C170") (pin "2") (pinfunction "2_2") (pintype "passive"))
      (node (ref "C184") (pin "2") (pinfunction "2_2") (pintype "passive"))
      (node (ref "C208") (pin "2") (pinfunction "2_2") (pintype "passive"))
      (node (ref "C215") (pin "2") (pinfunction "2_2") (pintype "passive"))
      (node (ref "C216") (pin "2") (pinfunction "2_2") (pintype "passive"))
      (node (ref "C217") (pin "2") (pinfunction "2_2") (pintype "passive"))
      (node (ref "C218") (pin "2") (pinfunction "2_2") (pintype "passive"))
      (node (ref "C219") (pin "2") (pinfunction "2_2") (pintype "passive"))
      (node (ref "C220") (pin "2") (pinfunction "2_2") (pintype "passive"))
      (node (ref "C221") (pin "2") (pinfunction "2_2") (pintype "passive"))
      (node (ref "C222") (pin "2") (pinfunction "2_2") (pintype "passive"))
      (node (ref "C223") (pin "2") (pinfunction "2_2") (pintype "passive"))
      (node (ref "C227") (pin "2") (pinfunction "2_2") (pintype "passive"))
      (node (ref "C228") (pin "2") (pinfunction "2_2") (pintype "passive"))
      (node (ref "C229") (pin "2") (pinfunction "2_2") (pintype "passive"))
      (node (ref "C230") (pin "2") (pinfunction "2_2") (pintype "passive"))
      (node (ref "C231") (pin "2") (pinfunction "2_2") (pintype "passive"))
      (node (ref "C232") (pin "2") (pinfunction "2_2") (pintype "passive"))
      (node (ref "C233") (pin "2") (pinfunction "2_2") (pintype "passive"))
      (node (ref "C235") (pin "2") (pinfunction "2_2") (pintype "passive"))
      (node (ref "C236") (pin "2") (pinfunction "2_2") (pintype "passive"))
      (node (ref "C237") (pin "2") (pinfunction "2_2") (pintype "passive"))
      (node (ref "C238") (pin "2") (pinfunction "2_2") (pintype "passive"))
      (node (ref "C239") (pin "2") (pinfunction "2_2") (pintype "passive"))
      (node (ref "C240") (pin "2") (pinfunction "2_2") (pintype "passive"))
      (node (ref "C241") (pin "2") (pinfunction "2_2") (pintype "passive"))
      (node (ref "C242") (pin "2") (pinfunction "2_2") (pintype "passive"))
      (node (ref "C243") (pin "2") (pinfunction "2_2") (pintype "passive"))
      (node (ref "C244") (pin "2") (pinfunction "2_2") (pintype "passive"))
      (node (ref "C245") (pin "2") (pinfunction "2_2") (pintype "passive"))
      (node (ref "C246") (pin "2") (pinfunction "2_2") (pintype "passive"))
      (node (ref "C247") (pin "2") (pinfunction "2_2") (pintype "passive"))
      (node (ref "C248") (pin "2") (pinfunction "2_2") (pintype "passive"))
      (node (ref "C250") (pin "2") (pinfunction "2_2") (pintype "passive"))
      (node (ref "C251") (pin "2") (pinfunction "2_2") (pintype "passive"))
      (node (ref "C252") (pin "2") (pinfunction "2_2") (pintype "passive"))
      (node (ref "C253") (pin "2") (pinfunction "2_2") (pintype "passive"))
      (node (ref "C254") (pin "2") (pinfunction "2_2") (pintype "passive"))
      (node (ref "C255") (pin "2") (pinfunction "2_2") (pintype "passive"))
      (node (ref "C256") (pin "2") (pinfunction "2_2") (pintype "passive"))
      (node (ref "C257") (pin "2") (pinfunction "2_2") (pintype "passive"))
      (node (ref "C258") (pin "2") (pinfunction "2_2") (pintype "passive"))
      (node (ref "C259") (pin "1") (pinfunction "1_1") (pintype "passive"))
      (node (ref "C260") (pin "2") (pinfunction "2_2") (pintype "passive"))
      (node (ref "C261") (pin "2") (pinfunction "2_2") (pintype "passive"))
      (node (ref "C262") (pin "2") (pinfunction "2_2") (pintype "passive"))
      (node (ref "C263") (pin "2") (pinfunction "2_2") (pintype "passive"))
      (node (ref "C264") (pin "2") (pinfunction "2_2") (pintype "passive"))
      (node (ref "C265") (pin "1") (pinfunction "1_1") (pintype "passive"))
      (node (ref "C55") (pin "2") (pinfunction "2_2") (pintype "passive"))
      (node (ref "C56") (pin "2") (pinfunction "2_2") (pintype "passive"))
      (node (ref "C59") (pin "2") (pinfunction "2_2") (pintype "passive"))
      (node (ref "C60") (pin "2") (pinfunction "2_2") (pintype "passive"))
      (node (ref "C61") (pin "2") (pinfunction "2_2") (pintype "passive"))
      (node (ref "C62") (pin "2") (pinfunction "2_2") (pintype "passive"))
      (node (ref "C63") (pin "2") (pinfunction "2_2") (pintype "passive"))
      (node (ref "C64") (pin "2") (pinfunction "2_2") (pintype "passive"))
      (node (ref "C68") (pin "2") (pinfunction "2_2") (pintype "passive"))
      (node (ref "C69") (pin "2") (pinfunction "2_2") (pintype "passive"))
      (node (ref "C71") (pin "2") (pinfunction "2_2") (pintype "passive"))
      (node (ref "C72") (pin "2") (pinfunction "2_2") (pintype "passive"))
      (node (ref "C73") (pin "2") (pinfunction "2_2") (pintype "passive"))
      (node (ref "C74") (pin "2") (pinfunction "2_2") (pintype "passive"))
      (node (ref "C75") (pin "2") (pinfunction "2_2") (pintype "passive"))
      (node (ref "C76") (pin "2") (pinfunction "2_2") (pintype "passive"))
      (node (ref "C77") (pin "2") (pinfunction "2_2") (pintype "passive"))
      (node (ref "C78") (pin "2") (pinfunction "2_2") (pintype "passive"))
      (node (ref "C79") (pin "2") (pinfunction "2_2") (pintype "passive"))
      (node (ref "C80") (pin "2") (pinfunction "2_2") (pintype "passive"))
      (node (ref "C81") (pin "2") (pinfunction "2_2") (pintype "passive"))
      (node (ref "C82") (pin "2") (pinfunction "2_2") (pintype "passive"))
      (node (ref "C83") (pin "2") (pinfunction "2_2") (pintype "passive"))
      (node (ref "C84") (pin "2") (pinfunction "2_2") (pintype "passive"))
      (node (ref "C85") (pin "2") (pinfunction "2_2") (pintype "passive"))
      (node (ref "C86") (pin "2") (pinfunction "2_2") (pintype "passive"))
      (node (ref "C87") (pin "2") (pinfunction "2_2") (pintype "passive"))
      (node (ref "C88") (pin "2") (pinfunction "2_2") (pintype "passive"))
      (node (ref "C89") (pin "2") (pinfunction "2_2") (pintype "passive"))
      (node (ref "C90") (pin "2") (pinfunction "2_2") (pintype "passive"))
      (node (ref "R180") (pin "1") (pinfunction "1_1") (pintype "passive"))
      (node (ref "Y1") (pin "3") (pinfunction "GND_3") (pintype "power_in"))
      (node (ref "Y2") (pin "5") (pinfunction "GND_5") (pintype "power_in"))
    )
    (net (code "23") (name "Net-(C249-Pad1)") (class "Default")
      (node (ref "C249") (pin "1") (pinfunction "1_1") (pintype "passive"))
      (node (ref "R178") (pin "1") (pinfunction "1_1") (pintype "passive"))
      (node (ref "R179") (pin "2") (pinfunction "2_2") (pintype "passive"))
      (node (ref "R180") (pin "2") (pinfunction "2_2") (pintype "passive"))
    )
    (net (code "24") (name "Net-(R183-Pad1)") (class "Default")
      (node (ref "R183") (pin "1") (pinfunction "1_1") (pintype "passive"))
      (node (ref "Y2") (pin "7") (pinfunction "NC_7") (pintype "passive"))
    )
    (net (code "25") (name "Net-(R184-Pad1)") (class "Default")
      (node (ref "R184") (pin "1") (pinfunction "1_1") (pintype "passive"))
      (node (ref "Y2") (pin "8") (pinfunction "NC_8") (pintype "passive"))
    )
    (net (code "26") (name "Net-(Y1-Output)") (class "Default")
      (node (ref "R179") (pin "1") (pinfunction "1_1") (pintype "passive"))
      (node (ref "Y1") (pin "4") (pinfunction "Output_4") (pintype "output"))
    )
    (net (code "27") (name "Net-(Y1-VDD)") (class "Default")
      (node (ref "C257") (pin "1") (pinfunction "1_1") (pintype "passive"))
      (node (ref "C258") (pin "1") (pinfunction "1_1") (pintype "passive"))
      (node (ref "L17") (pin "2") (pinfunction "2_2") (pintype "passive"))
      (node (ref "Y1") (pin "1") (pinfunction "~{Tri-State}_1") (pintype "input"))
      (node (ref "Y1") (pin "6") (pinfunction "VDD_6") (pintype "power_in"))
    )
    (net (code "28") (name "Net-(Y2-CLK)") (class "Default")
      (node (ref "R181") (pin "2") (pinfunction "2_2") (pintype "passive"))
      (node (ref "Y2") (pin "6") (pinfunction "CLK_6") (pintype "output"))
    )
    (net (code "29") (name "Net-(Y2-OE)") (class "Default")
      (node (ref "R182") (pin "2") (pinfunction "2_2") (pintype "passive"))
      (node (ref "Y2") (pin "1") (pinfunction "OE_1") (pintype "input"))
    )
    (net (code "30") (name "Net-(Y2-VDD)") (class "Default")
      (node (ref "C264") (pin "1") (pinfunction "1_1") (pintype "passive"))
      (node (ref "C265") (pin "2") (pinfunction "2_2") (pintype "passive"))
      (node (ref "FB7") (pin "1") (pinfunction "1_1") (pintype "passive"))
      (node (ref "R182") (pin "1") (pinfunction "1_1") (pintype "passive"))
      (node (ref "Y2") (pin "10") (pinfunction "VDD_10") (pintype "power_in"))
    )
    (net (code "31") (name "P1V8") (class "Default")
      (node (ref "C217") (pin "1") (pinfunction "1_1") (pintype "passive"))
      (node (ref "C231") (pin "1") (pinfunction "1_1") (pintype "passive"))
      (node (ref "C246") (pin "1") (pinfunction "1_1") (pintype "passive"))
      (node (ref "C76") (pin "1") (pinfunction "1_1") (pintype "passive"))
      (node (ref "C77") (pin "1") (pinfunction "1_1") (pintype "passive"))
      (node (ref "C78") (pin "1") (pinfunction "1_1") (pintype "passive"))
      (node (ref "C86") (pin "1") (pinfunction "1_1") (pintype "passive"))
      (node (ref "L10") (pin "1") (pinfunction "1_1") (pintype "passive"))
      (node (ref "L14") (pin "1") (pinfunction "1_1") (pintype "passive"))
      (node (ref "L3") (pin "1") (pinfunction "1_1") (pintype "passive"))
      (node (ref "L4") (pin "1") (pinfunction "1_1") (pintype "passive"))
      (node (ref "L7") (pin "1") (pinfunction "1_1") (pintype "passive"))
      (node (ref "R175") (pin "1") (pinfunction "1_1") (pintype "passive"))
    )
    (net (code "32") (name "P3V3") (class "Default")
      (node (ref "C208") (pin "1") (pinfunction "1_1") (pintype "passive"))
      (node (ref "C218") (pin "1") (pinfunction "1_1") (pintype "passive"))
      (node (ref "C219") (pin "1") (pinfunction "1_1") (pintype "passive"))
      (node (ref "C222") (pin "1") (pinfunction "1_1") (pintype "passive"))
      (node (ref "C223") (pin "1") (pinfunction "1_1") (pintype "passive"))
      (node (ref "C235") (pin "1") (pinfunction "1_1") (pintype "passive"))
      (node (ref "C236") (pin "1") (pinfunction "1_1") (pintype "passive"))
      (node (ref "C237") (pin "1") (pinfunction "1_1") (pintype "passive"))
      (node (ref "C240") (pin "1") (pinfunction "1_1") (pintype "passive"))
      (node (ref "C241") (pin "1") (pinfunction "1_1") (pintype "passive"))
      (node (ref "C250") (pin "1") (pinfunction "1_1") (pintype "passive"))
      (node (ref "C251") (pin "1") (pinfunction "1_1") (pintype "passive"))
      (node (ref "C252") (pin "1") (pinfunction "1_1") (pintype "passive"))
      (node (ref "C255") (pin "1") (pinfunction "1_1") (pintype "passive"))
      (node (ref "C256") (pin "1") (pinfunction "1_1") (pintype "passive"))
      (node (ref "C259") (pin "2") (pinfunction "2_2") (pintype "passive"))
      (node (ref "C260") (pin "1") (pinfunction "1_1") (pintype "passive"))
      (node (ref "C261") (pin "1") (pinfunction "1_1") (pintype "passive"))
      (node (ref "C55") (pin "1") (pinfunction "1_1") (pintype "passive"))
      (node (ref "C56") (pin "1") (pinfunction "1_1") (pintype "passive"))
      (node (ref "C74") (pin "1") (pinfunction "1_1") (pintype "passive"))
      (node (ref "C75") (pin "1") (pinfunction "1_1") (pintype "passive"))
      (node (ref "C79") (pin "1") (pinfunction "1_1") (pintype "passive"))
      (node (ref "C82") (pin "1") (pinfunction "1_1") (pintype "passive"))
      (node (ref "C83") (pin "1") (pinfunction "1_1") (pintype "passive"))
      (node (ref "FB7") (pin "2") (pinfunction "2_2") (pintype "passive"))
      (node (ref "L1") (pin "1") (pinfunction "1_1") (pintype "passive"))
      (node (ref "L11") (pin "1") (pinfunction "1_1") (pintype "passive"))
      (node (ref "L12") (pin "1") (pinfunction "1_1") (pintype "passive"))
      (node (ref "L13") (pin "1") (pinfunction "1_1") (pintype "passive"))
      (node (ref "L15") (pin "1") (pinfunction "1_1") (pintype "passive"))
      (node (ref "L16") (pin "1") (pinfunction "1_1") (pintype "passive"))
      (node (ref "L17") (pin "1") (pinfunction "1_1") (pintype "passive"))
      (node (ref "L18") (pin "1") (pinfunction "1_1") (pintype "passive"))
      (node (ref "L2") (pin "1") (pinfunction "1_1") (pintype "passive"))
      (node (ref "L5") (pin "1") (pinfunction "1_1") (pintype "passive"))
      (node (ref "L6") (pin "1") (pinfunction "1_1") (pintype "passive"))
      (node (ref "L8") (pin "1") (pinfunction "1_1") (pintype "passive"))
      (node (ref "L9") (pin "1") (pinfunction "1_1") (pintype "passive"))
      (node (ref "R177") (pin "1") (pinfunction "1_1") (pintype "passive"))
      (node (ref "R178") (pin "2") (pinfunction "2_2") (pintype "passive"))
      (node (ref "R183") (pin "2") (pinfunction "2_2") (pintype "passive"))
      (node (ref "R184") (pin "2") (pinfunction "2_2") (pintype "passive"))
    )
    (net (code "33") (name "SiT5501_PLL_SCL") (class "Default")
      (node (ref "Y2") (pin "3") (pinfunction "NC_3") (pintype "passive"))
    )
    (net (code "34") (name "SiT5501_PLL_SDA") (class "Default")
      (node (ref "Y2") (pin "2") (pinfunction "NC_2") (pintype "passive"))
    )
    (net (code "35") (name "unconnected-(Y2-NC-Pad4)") (class "Default")
      (node (ref "Y2") (pin "4") (pinfunction "NC_4") (pintype "passive"))
    )
    (net (code "36") (name "unconnected-(Y2-NC-Pad9)") (class "Default")
      (node (ref "Y2") (pin "9") (pinfunction "NC_9") (pintype "passive"))
    )
  )
)
